# FrSky_DJT_Decoder_2020-07-06_10-18-27.net
KiCad netlist of a schematic drawn in EasyEDA
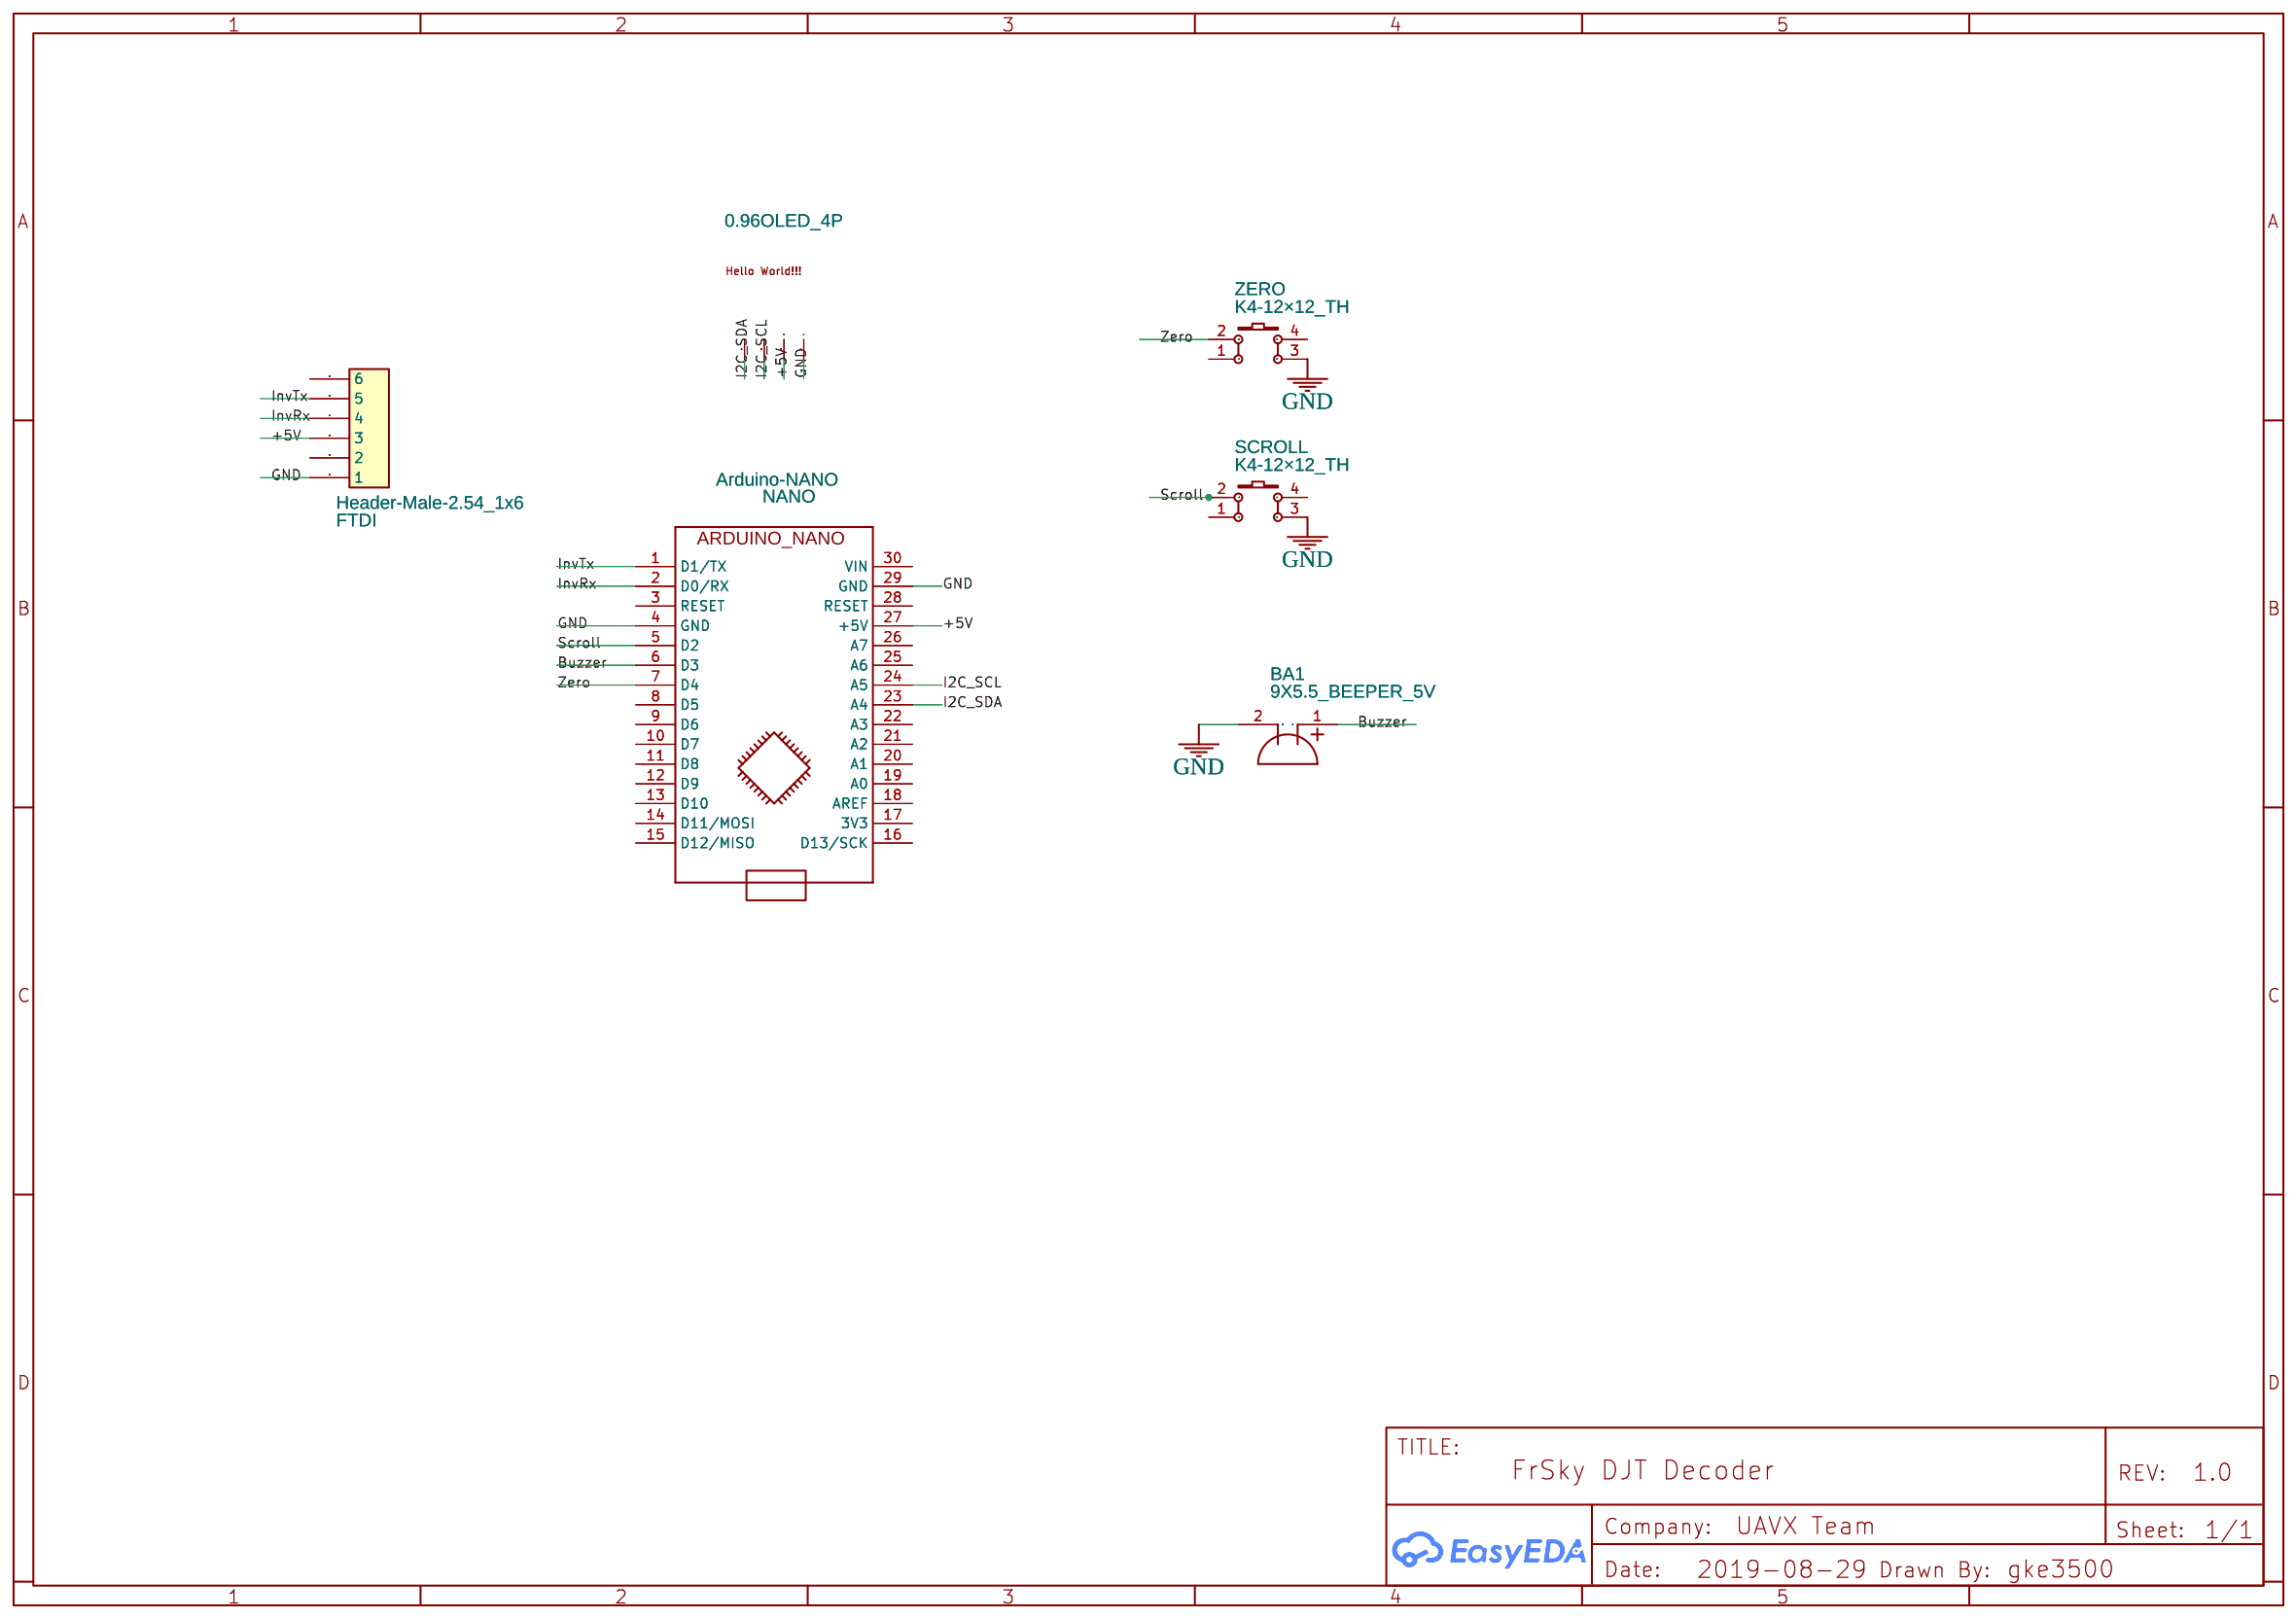
[diagram p0: schematic sheet]

(export (version "E")
  (design (tool "Eeschema 10.0.6"))
  (components
    (comp (ref "BA1") (value "9X5.5_BEEPER_5V") (libsource (lib "") (part "9X5.5_BEEPER_5V")))
    (comp (ref "FTDI")
      (value "Header-Male-2.54_1x6")
      (fields (field (name "BOM_Supplier Part") "C37208"))
      (libsource (lib "") (part "Header-Male-2.54_1x6"))
    )
    (comp (ref "NANO")
      (value "Arduino-NANO")
      (fields (field (name "BOM_Supplier Part") "undefined"))
      (libsource (lib "") (part "Unknown_385_350"))
    )
    (comp (ref "OLED") (value "0.96OLED_4P") (libsource (lib "") (part "0.96OLED_4P")))
    (comp (ref "SCROLL")
      (value "K4-12×12_TH")
      (fields
        (field (name "BOM_Manufacturer Part") "K2-1103DP-M4SW-04")
        (field (name "BOM_Supplier Part") "C128053")
      )
      (libsource (lib "") (part "K4-12×12_TH"))
    )
    (comp (ref "ZERO")
      (value "K4-12×12_TH")
      (fields
        (field (name "BOM_Manufacturer Part") "K2-1103DP-M4SW-04")
        (field (name "BOM_Supplier Part") "C128053")
      )
      (libsource (lib "") (part "K4-12×12_TH_1"))
    )
  )
  (nets
    (net (code "1") (name "/+5V") (class "Default")
      (node (ref "FTDI") (pin "3") (pinfunction "3_3") (pintype "input"))
      (node (ref "NANO") (pin "27") (pinfunction "+5V_27") (pintype "unspecified"))
      (node (ref "OLED") (pin "3") (pinfunction "3_3") (pintype "unspecified"))
    )
    (net (code "2") (name "/Buzzer") (class "Default")
      (node (ref "BA1") (pin "1") (pinfunction "1_1") (pintype "unspecified"))
      (node (ref "NANO") (pin "6") (pinfunction "D3_6") (pintype "unspecified"))
    )
    (net (code "3") (name "/I2C_SCL") (class "Default")
      (node (ref "NANO") (pin "24") (pinfunction "A5_24") (pintype "unspecified"))
      (node (ref "OLED") (pin "2") (pinfunction "2_2") (pintype "unspecified"))
    )
    (net (code "4") (name "/I2C_SDA") (class "Default")
      (node (ref "NANO") (pin "23") (pinfunction "A4_23") (pintype "unspecified"))
      (node (ref "OLED") (pin "1") (pinfunction "1_1") (pintype "unspecified"))
    )
    (net (code "5") (name "/InvRx") (class "Default")
      (node (ref "FTDI") (pin "4") (pinfunction "4_4") (pintype "input"))
      (node (ref "NANO") (pin "2") (pinfunction "D0/RX_2") (pintype "unspecified"))
    )
    (net (code "6") (name "/InvTx") (class "Default")
      (node (ref "FTDI") (pin "5") (pinfunction "5_5") (pintype "input"))
      (node (ref "NANO") (pin "1") (pinfunction "D1/TX_1") (pintype "unspecified"))
    )
    (net (code "7") (name "/Scroll") (class "Default")
      (node (ref "NANO") (pin "5") (pinfunction "D2_5") (pintype "unspecified"))
      (node (ref "SCROLL") (pin "2") (pinfunction "2_2") (pintype "unspecified"))
    )
    (net (code "8") (name "/Zero") (class "Default")
      (node (ref "NANO") (pin "7") (pinfunction "D4_7") (pintype "unspecified"))
      (node (ref "ZERO") (pin "2") (pinfunction "2_2") (pintype "unspecified"))
    )
    (net (code "9") (name "GND") (class "Default")
      (node (ref "BA1") (pin "2") (pinfunction "2_2") (pintype "unspecified"))
      (node (ref "FTDI") (pin "1") (pinfunction "1_1") (pintype "input"))
      (node (ref "NANO") (pin "29") (pinfunction "GND_29") (pintype "unspecified"))
      (node (ref "NANO") (pin "4") (pinfunction "GND_4") (pintype "unspecified"))
      (node (ref "OLED") (pin "4") (pinfunction "4_4") (pintype "unspecified"))
      (node (ref "SCROLL") (pin "3") (pinfunction "3_3") (pintype "unspecified"))
      (node (ref "ZERO") (pin "3") (pinfunction "3_3") (pintype "unspecified"))
    )
    (net (code "10") (name "unconnected-(FTDI-Pad2)") (class "Default")
      (node (ref "FTDI") (pin "2") (pinfunction "2_2") (pintype "input"))
    )
    (net (code "11") (name "unconnected-(FTDI-Pad6)") (class "Default")
      (node (ref "FTDI") (pin "6") (pinfunction "6_6") (pintype "input"))
    )
    (net (code "12") (name "unconnected-(NANO-3V3-Pad17)") (class "Default")
      (node (ref "NANO") (pin "17") (pinfunction "3V3_17") (pintype "unspecified"))
    )
    (net (code "13") (name "unconnected-(NANO-A0-Pad19)") (class "Default")
      (node (ref "NANO") (pin "19") (pinfunction "A0_19") (pintype "unspecified"))
    )
    (net (code "14") (name "unconnected-(NANO-A1-Pad20)") (class "Default")
      (node (ref "NANO") (pin "20") (pinfunction "A1_20") (pintype "unspecified"))
    )
    (net (code "15") (name "unconnected-(NANO-A2-Pad21)") (class "Default")
      (node (ref "NANO") (pin "21") (pinfunction "A2_21") (pintype "unspecified"))
    )
    (net (code "16") (name "unconnected-(NANO-A3-Pad22)") (class "Default")
      (node (ref "NANO") (pin "22") (pinfunction "A3_22") (pintype "unspecified"))
    )
    (net (code "17") (name "unconnected-(NANO-A6-Pad25)") (class "Default")
      (node (ref "NANO") (pin "25") (pinfunction "A6_25") (pintype "unspecified"))
    )
    (net (code "18") (name "unconnected-(NANO-A7-Pad26)") (class "Default")
      (node (ref "NANO") (pin "26") (pinfunction "A7_26") (pintype "unspecified"))
    )
    (net (code "19") (name "unconnected-(NANO-AREF-Pad18)") (class "Default")
      (node (ref "NANO") (pin "18") (pinfunction "AREF_18") (pintype "unspecified"))
    )
    (net (code "20") (name "unconnected-(NANO-D5-Pad8)") (class "Default")
      (node (ref "NANO") (pin "8") (pinfunction "D5_8") (pintype "unspecified"))
    )
    (net (code "21") (name "unconnected-(NANO-D6-Pad9)") (class "Default")
      (node (ref "NANO") (pin "9") (pinfunction "D6_9") (pintype "unspecified"))
    )
    (net (code "22") (name "unconnected-(NANO-D7-Pad10)") (class "Default")
      (node (ref "NANO") (pin "10") (pinfunction "D7_10") (pintype "unspecified"))
    )
    (net (code "23") (name "unconnected-(NANO-D8-Pad11)") (class "Default")
      (node (ref "NANO") (pin "11") (pinfunction "D8_11") (pintype "unspecified"))
    )
    (net (code "24") (name "unconnected-(NANO-D9-Pad12)") (class "Default")
      (node (ref "NANO") (pin "12") (pinfunction "D9_12") (pintype "unspecified"))
    )
    (net (code "25") (name "unconnected-(NANO-D10-Pad13)") (class "Default")
      (node (ref "NANO") (pin "13") (pinfunction "D10_13") (pintype "unspecified"))
    )
    (net (code "26") (name "unconnected-(NANO-D11{slash}MOSI-Pad14)") (class "Default")
      (node (ref "NANO") (pin "14") (pinfunction "D11/MOSI_14") (pintype "unspecified"))
    )
    (net (code "27") (name "unconnected-(NANO-D12{slash}MISO-Pad15)") (class "Default")
      (node (ref "NANO") (pin "15") (pinfunction "D12/MISO_15") (pintype "unspecified"))
    )
    (net (code "28") (name "unconnected-(NANO-D13{slash}SCK-Pad16)") (class "Default")
      (node (ref "NANO") (pin "16") (pinfunction "D13/SCK_16") (pintype "unspecified"))
    )
    (net (code "29") (name "unconnected-(NANO-RESET-Pad3)") (class "Default")
      (node (ref "NANO") (pin "3") (pinfunction "RESET_3") (pintype "unspecified"))
    )
    (net (code "30") (name "unconnected-(NANO-RESET-Pad28)") (class "Default")
      (node (ref "NANO") (pin "28") (pinfunction "RESET_28") (pintype "unspecified"))
    )
    (net (code "31") (name "unconnected-(NANO-VIN-Pad30)") (class "Default")
      (node (ref "NANO") (pin "30") (pinfunction "VIN_30") (pintype "unspecified"))
    )
    (net (code "32") (name "unconnected-(SCROLL-Pad1)") (class "Default")
      (node (ref "SCROLL") (pin "1") (pinfunction "1_1") (pintype "unspecified"))
    )
    (net (code "33") (name "unconnected-(SCROLL-Pad4)") (class "Default")
      (node (ref "SCROLL") (pin "4") (pinfunction "4_4") (pintype "unspecified"))
    )
    (net (code "34") (name "unconnected-(ZERO-Pad1)") (class "Default")
      (node (ref "ZERO") (pin "1") (pinfunction "1_1") (pintype "unspecified"))
    )
    (net (code "35") (name "unconnected-(ZERO-Pad4)") (class "Default")
      (node (ref "ZERO") (pin "4") (pinfunction "4_4") (pintype "unspecified"))
    )
  )
)
